# PCB_MCH_mordovia.net
KiCad netlist of a schematic drawn in Altium Designer
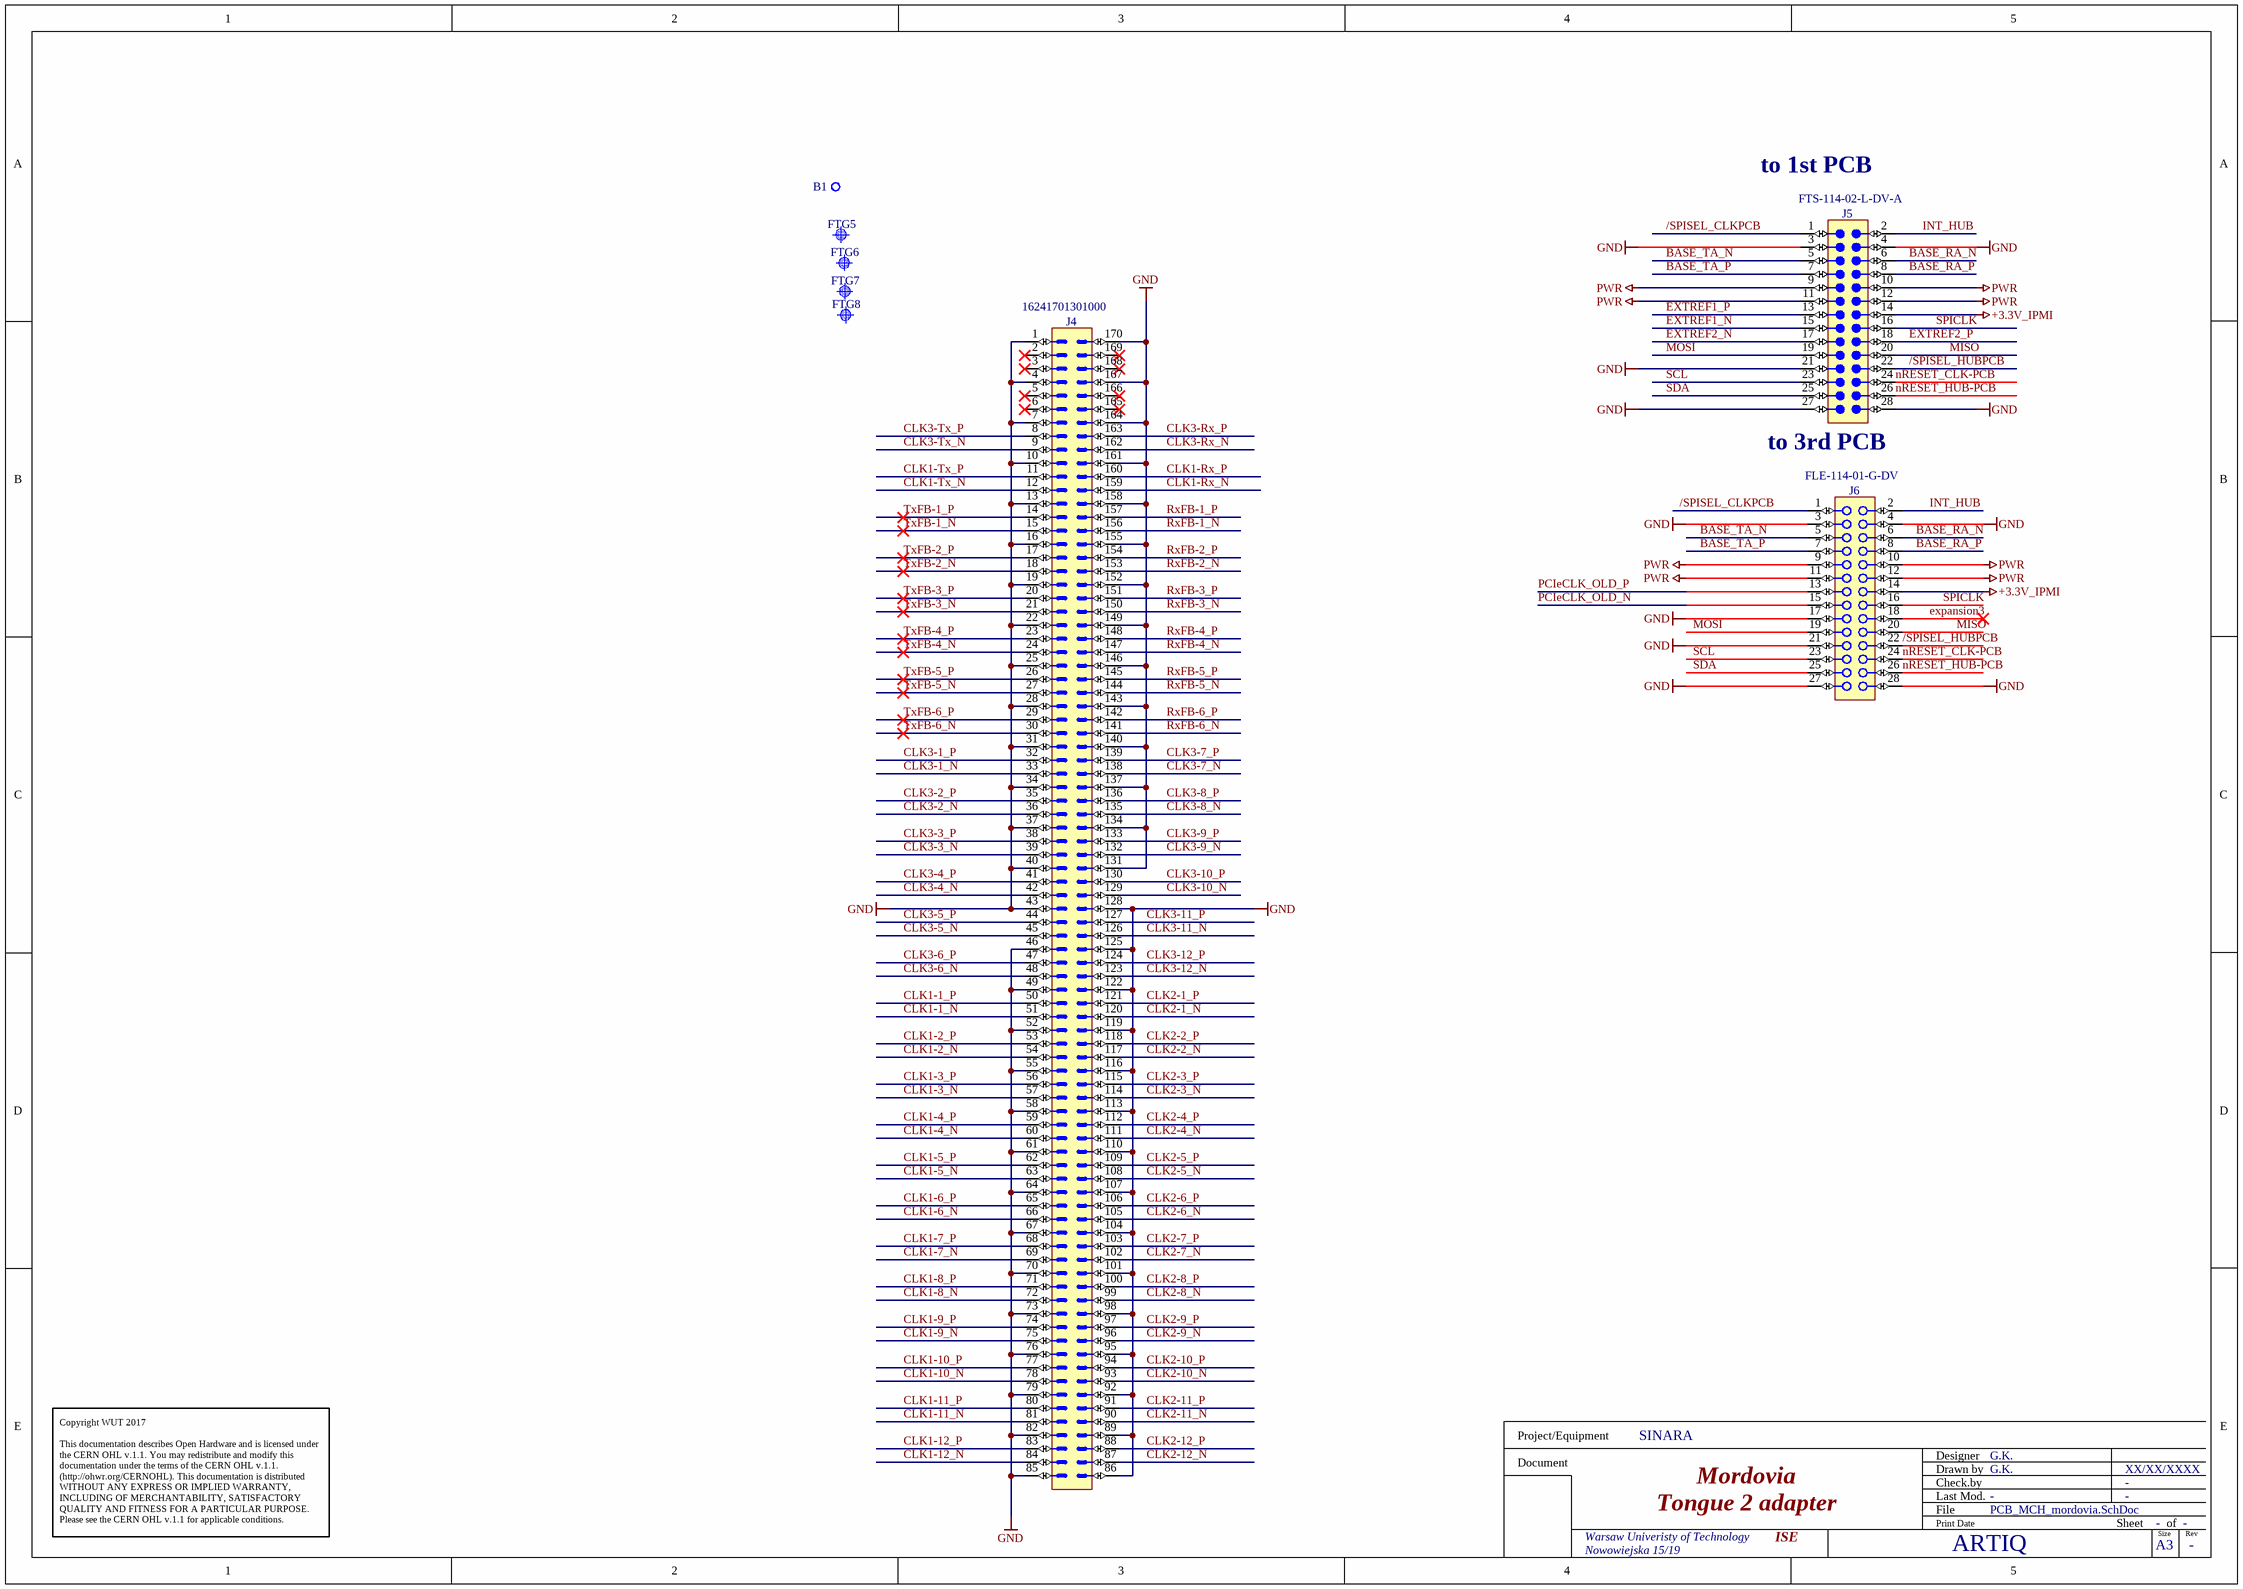
[diagram p0: PCB_MCH_mordovia.SchDoc]

(export (version "E")
  (design (tool "Eeschema 10.0.6"))
  (components
    (comp (ref "B1")
      (value "Non Plated Hole")
      (footprint "MTG520")
      (description "Single Terminal Socket")
      (fields (field (name "PART NUMBER") "NON-PLATED_HOLE5.2") (field (name "AUTHOR") "CERN DEM JMW"))
      (libsource (lib "Eletro-mechanical") (part "Single Terminal Socket"))
    )
    (comp (ref "FTG5")
      (value "Use only in PCB")
      (footprint "FIDUCIAL_TOP_C100-200")
      (description "Fiducial Target")
      (fields (field (name "PART NUMBER") "FIDUCIAL_TARGET_C100-200") (field (name "AUTHOR") "CERN DEM JLC"))
      (libsource (lib "Eletro-mechanical") (part "Fiducial Target"))
    )
    (comp (ref "FTG6")
      (value "Use only in PCB")
      (footprint "FIDUCIAL_TOP_S100-200")
      (description "Fiducial Target")
      (fields (field (name "PART NUMBER") "FIDUCIAL_TARGET_S100-200") (field (name "AUTHOR") "CERN DEM JLC"))
      (libsource (lib "Eletro-mechanical") (part "Fiducial Target"))
    )
    (comp (ref "FTG7")
      (value "Use only in PCB")
      (footprint "FIDUCIAL_TOP_S200-400")
      (description "Fiducial Target")
      (fields (field (name "PART NUMBER") "FIDUCIAL_TARGET_S200-400") (field (name "AUTHOR") "CERN DEM JLC"))
      (libsource (lib "Eletro-mechanical") (part "Fiducial Target"))
    )
    (comp (ref "FTG8")
      (value "Use only in PCB")
      (footprint "FIDUCIAL_TOP_S100-200")
      (description "Fiducial Target")
      (fields (field (name "PART NUMBER") "FIDUCIAL_TARGET_S100-200") (field (name "AUTHOR") "CERN DEM JLC"))
      (libsource (lib "Eletro-mechanical") (part "Fiducial Target"))
    )
    (comp (ref "J4")
      (value "~")
      (footprint "ITB_16241701301000")
      (description "Connector 170 Male")
      (fields
        (field (name "PART NUMBER") "ITB_16241701301000")
        (field (name "MANUFACTURER") "ITB ADVANCED CONNECTORS")
        (field (name "MANUFACTURER PART NUMBER") "16241701301000")
        (field (name "AUTHOR") "CERN DEM MR")
      )
      (libsource (lib "Connectors") (part "Connector 170 Male"))
    )
    (comp (ref "J5")
      (value "Header 28")
      (footprint "SAMTEC_FTS-114-02-L-DV-A")
      (description "Connector 28 Male")
      (fields
        (field (name "PART NUMBER") "SAMTEC_FTS-114-02-L-DV-A")
        (field (name "MANUFACTURER") "SAMTEC")
        (field (name "MANUFACTURER PART NUMBER") "FTS-114-02-L-DV-A")
        (field (name "AUTHOR") "CERN DEM MR")
      )
      (libsource (lib "Connectors") (part "Connector 28 Male"))
    )
    (comp (ref "J6")
      (value "Socket 28")
      (footprint "SAMTEC_FLE-114-01-G-DV")
      (description "Connector 28 Female")
      (fields
        (field (name "PART NUMBER") "SAMTEC_FLE-114-01-G-DV")
        (field (name "MANUFACTURER") "SAMTEC")
        (field (name "MANUFACTURER PART NUMBER") "FLE-114-01-G-DV")
        (field (name "AUTHOR") "CERN DEM MR")
      )
      (libsource (lib "Connectors") (part "Connector 28 Female"))
    )
  )
  (nets
    (net (code "1") (name "+3.3V_IPMI") (class "Default")
      (node (ref "J5") (pin "14") (pinfunction "14_14") (pintype "bidirectional"))
      (node (ref "J6") (pin "14") (pinfunction "14_14") (pintype "bidirectional"))
    )
    (net (code "2") (name "/BASE_RA_N") (class "Default")
      (node (ref "J5") (pin "6") (pinfunction "6_6") (pintype "bidirectional"))
      (node (ref "J6") (pin "6") (pinfunction "6_6") (pintype "bidirectional"))
    )
    (net (code "3") (name "/BASE_RA_P") (class "Default")
      (node (ref "J5") (pin "8") (pinfunction "8_8") (pintype "bidirectional"))
      (node (ref "J6") (pin "8") (pinfunction "8_8") (pintype "bidirectional"))
    )
    (net (code "4") (name "/BASE_TA_N") (class "Default")
      (node (ref "J5") (pin "5") (pinfunction "5_5") (pintype "bidirectional"))
      (node (ref "J6") (pin "5") (pinfunction "5_5") (pintype "bidirectional"))
    )
    (net (code "5") (name "/BASE_TA_P") (class "Default")
      (node (ref "J5") (pin "7") (pinfunction "7_7") (pintype "bidirectional"))
      (node (ref "J6") (pin "7") (pinfunction "7_7") (pintype "bidirectional"))
    )
    (net (code "6") (name "/CLK1-1_N") (class "Default")
      (node (ref "J4") (pin "51") (pinfunction "101_51") (pintype "bidirectional"))
    )
    (net (code "7") (name "/CLK1-1_P") (class "Default")
      (node (ref "J4") (pin "50") (pinfunction "99_50") (pintype "bidirectional"))
    )
    (net (code "8") (name "/CLK1-2_N") (class "Default")
      (node (ref "J4") (pin "54") (pinfunction "107_54") (pintype "bidirectional"))
    )
    (net (code "9") (name "/CLK1-2_P") (class "Default")
      (node (ref "J4") (pin "53") (pinfunction "105_53") (pintype "bidirectional"))
    )
    (net (code "10") (name "/CLK1-3_N") (class "Default")
      (node (ref "J4") (pin "57") (pinfunction "113_57") (pintype "bidirectional"))
    )
    (net (code "11") (name "/CLK1-3_P") (class "Default")
      (node (ref "J4") (pin "56") (pinfunction "111_56") (pintype "bidirectional"))
    )
    (net (code "12") (name "/CLK1-4_N") (class "Default")
      (node (ref "J4") (pin "60") (pinfunction "119_60") (pintype "bidirectional"))
    )
    (net (code "13") (name "/CLK1-4_P") (class "Default")
      (node (ref "J4") (pin "59") (pinfunction "117_59") (pintype "bidirectional"))
    )
    (net (code "14") (name "/CLK1-5_N") (class "Default")
      (node (ref "J4") (pin "63") (pinfunction "75_63") (pintype "bidirectional"))
    )
    (net (code "15") (name "/CLK1-5_P") (class "Default")
      (node (ref "J4") (pin "62") (pinfunction "73_62") (pintype "bidirectional"))
    )
    (net (code "16") (name "/CLK1-6_N") (class "Default")
      (node (ref "J4") (pin "66") (pinfunction "81_66") (pintype "bidirectional"))
    )
    (net (code "17") (name "/CLK1-6_P") (class "Default")
      (node (ref "J4") (pin "65") (pinfunction "79_65") (pintype "bidirectional"))
    )
    (net (code "18") (name "/CLK1-7_N") (class "Default")
      (node (ref "J4") (pin "69") (pinfunction "87_69") (pintype "bidirectional"))
    )
    (net (code "19") (name "/CLK1-7_P") (class "Default")
      (node (ref "J4") (pin "68") (pinfunction "85_68") (pintype "bidirectional"))
    )
    (net (code "20") (name "/CLK1-8_N") (class "Default")
      (node (ref "J4") (pin "72") (pinfunction "93_72") (pintype "bidirectional"))
    )
    (net (code "21") (name "/CLK1-8_P") (class "Default")
      (node (ref "J4") (pin "71") (pinfunction "91_71") (pintype "bidirectional"))
    )
    (net (code "22") (name "/CLK1-9_N") (class "Default")
      (node (ref "J4") (pin "75") (pinfunction "99_75") (pintype "bidirectional"))
    )
    (net (code "23") (name "/CLK1-9_P") (class "Default")
      (node (ref "J4") (pin "74") (pinfunction "97_74") (pintype "bidirectional"))
    )
    (net (code "24") (name "/CLK1-10_N") (class "Default")
      (node (ref "J4") (pin "78") (pinfunction "105_78") (pintype "bidirectional"))
    )
    (net (code "25") (name "/CLK1-10_P") (class "Default")
      (node (ref "J4") (pin "77") (pinfunction "103_77") (pintype "bidirectional"))
    )
    (net (code "26") (name "/CLK1-11_N") (class "Default")
      (node (ref "J4") (pin "81") (pinfunction "111_81") (pintype "bidirectional"))
    )
    (net (code "27") (name "/CLK1-11_P") (class "Default")
      (node (ref "J4") (pin "80") (pinfunction "109_80") (pintype "bidirectional"))
    )
    (net (code "28") (name "/CLK1-12_N") (class "Default")
      (node (ref "J4") (pin "84") (pinfunction "117_84") (pintype "bidirectional"))
    )
    (net (code "29") (name "/CLK1-12_P") (class "Default")
      (node (ref "J4") (pin "83") (pinfunction "115_83") (pintype "bidirectional"))
    )
    (net (code "30") (name "/CLK1-Rx_N") (class "Default")
      (node (ref "J4") (pin "159") (pinfunction "159_159") (pintype "bidirectional"))
    )
    (net (code "31") (name "/CLK1-Rx_P") (class "Default")
      (node (ref "J4") (pin "160") (pinfunction "160_160") (pintype "bidirectional"))
    )
    (net (code "32") (name "/CLK1-Tx_N") (class "Default")
      (node (ref "J4") (pin "12") (pinfunction "23_12") (pintype "bidirectional"))
    )
    (net (code "33") (name "/CLK1-Tx_P") (class "Default")
      (node (ref "J4") (pin "11") (pinfunction "21_11") (pintype "bidirectional"))
    )
    (net (code "34") (name "/CLK2-1_N") (class "Default")
      (node (ref "J4") (pin "120") (pinfunction "120_120") (pintype "bidirectional"))
    )
    (net (code "35") (name "/CLK2-1_P") (class "Default")
      (node (ref "J4") (pin "121") (pinfunction "121_121") (pintype "bidirectional"))
    )
    (net (code "36") (name "/CLK2-2_N") (class "Default")
      (node (ref "J4") (pin "117") (pinfunction "117_117") (pintype "bidirectional"))
    )
    (net (code "37") (name "/CLK2-2_P") (class "Default")
      (node (ref "J4") (pin "118") (pinfunction "118_118") (pintype "bidirectional"))
    )
    (net (code "38") (name "/CLK2-3_N") (class "Default")
      (node (ref "J4") (pin "114") (pinfunction "114_114") (pintype "bidirectional"))
    )
    (net (code "39") (name "/CLK2-3_P") (class "Default")
      (node (ref "J4") (pin "115") (pinfunction "115_115") (pintype "bidirectional"))
    )
    (net (code "40") (name "/CLK2-4_N") (class "Default")
      (node (ref "J4") (pin "111") (pinfunction "111_111") (pintype "bidirectional"))
    )
    (net (code "41") (name "/CLK2-4_P") (class "Default")
      (node (ref "J4") (pin "112") (pinfunction "112_112") (pintype "bidirectional"))
    )
    (net (code "42") (name "/CLK2-5_N") (class "Default")
      (node (ref "J4") (pin "108") (pinfunction "108_108") (pintype "bidirectional"))
    )
    (net (code "43") (name "/CLK2-5_P") (class "Default")
      (node (ref "J4") (pin "109") (pinfunction "109_109") (pintype "bidirectional"))
    )
    (net (code "44") (name "/CLK2-6_N") (class "Default")
      (node (ref "J4") (pin "105") (pinfunction "105_105") (pintype "bidirectional"))
    )
    (net (code "45") (name "/CLK2-6_P") (class "Default")
      (node (ref "J4") (pin "106") (pinfunction "106_106") (pintype "bidirectional"))
    )
    (net (code "46") (name "/CLK2-7_N") (class "Default")
      (node (ref "J4") (pin "102") (pinfunction "102_102") (pintype "bidirectional"))
    )
    (net (code "47") (name "/CLK2-7_P") (class "Default")
      (node (ref "J4") (pin "103") (pinfunction "103_103") (pintype "bidirectional"))
    )
    (net (code "48") (name "/CLK2-8_N") (class "Default")
      (node (ref "J4") (pin "99") (pinfunction "99_99") (pintype "bidirectional"))
    )
    (net (code "49") (name "/CLK2-8_P") (class "Default")
      (node (ref "J4") (pin "100") (pinfunction "100_100") (pintype "bidirectional"))
    )
    (net (code "50") (name "/CLK2-9_N") (class "Default")
      (node (ref "J4") (pin "96") (pinfunction "96_96") (pintype "bidirectional"))
    )
    (net (code "51") (name "/CLK2-9_P") (class "Default")
      (node (ref "J4") (pin "97") (pinfunction "97_97") (pintype "bidirectional"))
    )
    (net (code "52") (name "/CLK2-10_N") (class "Default")
      (node (ref "J4") (pin "93") (pinfunction "93_93") (pintype "bidirectional"))
    )
    (net (code "53") (name "/CLK2-10_P") (class "Default")
      (node (ref "J4") (pin "94") (pinfunction "94_94") (pintype "bidirectional"))
    )
    (net (code "54") (name "/CLK2-11_N") (class "Default")
      (node (ref "J4") (pin "90") (pinfunction "90_90") (pintype "bidirectional"))
    )
    (net (code "55") (name "/CLK2-11_P") (class "Default")
      (node (ref "J4") (pin "91") (pinfunction "91_91") (pintype "bidirectional"))
    )
    (net (code "56") (name "/CLK2-12_N") (class "Default")
      (node (ref "J4") (pin "87") (pinfunction "87_87") (pintype "bidirectional"))
    )
    (net (code "57") (name "/CLK2-12_P") (class "Default")
      (node (ref "J4") (pin "88") (pinfunction "88_88") (pintype "bidirectional"))
    )
    (net (code "58") (name "/CLK3-1_N") (class "Default")
      (node (ref "J4") (pin "33") (pinfunction "65_33") (pintype "bidirectional"))
    )
    (net (code "59") (name "/CLK3-1_P") (class "Default")
      (node (ref "J4") (pin "32") (pinfunction "63_32") (pintype "bidirectional"))
    )
    (net (code "60") (name "/CLK3-2_N") (class "Default")
      (node (ref "J4") (pin "36") (pinfunction "71_36") (pintype "bidirectional"))
    )
    (net (code "61") (name "/CLK3-2_P") (class "Default")
      (node (ref "J4") (pin "35") (pinfunction "69_35") (pintype "bidirectional"))
    )
    (net (code "62") (name "/CLK3-3_N") (class "Default")
      (node (ref "J4") (pin "39") (pinfunction "77_39") (pintype "bidirectional"))
    )
    (net (code "63") (name "/CLK3-3_P") (class "Default")
      (node (ref "J4") (pin "38") (pinfunction "75_38") (pintype "bidirectional"))
    )
    (net (code "64") (name "/CLK3-4_N") (class "Default")
      (node (ref "J4") (pin "42") (pinfunction "83_42") (pintype "bidirectional"))
    )
    (net (code "65") (name "/CLK3-4_P") (class "Default")
      (node (ref "J4") (pin "41") (pinfunction "81_41") (pintype "bidirectional"))
    )
    (net (code "66") (name "/CLK3-5_N") (class "Default")
      (node (ref "J4") (pin "45") (pinfunction "89_45") (pintype "bidirectional"))
    )
    (net (code "67") (name "/CLK3-5_P") (class "Default")
      (node (ref "J4") (pin "44") (pinfunction "87_44") (pintype "bidirectional"))
    )
    (net (code "68") (name "/CLK3-6_N") (class "Default")
      (node (ref "J4") (pin "48") (pinfunction "95_48") (pintype "bidirectional"))
    )
    (net (code "69") (name "/CLK3-6_P") (class "Default")
      (node (ref "J4") (pin "47") (pinfunction "93_47") (pintype "bidirectional"))
    )
    (net (code "70") (name "/CLK3-7_N") (class "Default")
      (node (ref "J4") (pin "138") (pinfunction "138_138") (pintype "bidirectional"))
    )
    (net (code "71") (name "/CLK3-7_P") (class "Default")
      (node (ref "J4") (pin "139") (pinfunction "139_139") (pintype "bidirectional"))
    )
    (net (code "72") (name "/CLK3-8_N") (class "Default")
      (node (ref "J4") (pin "135") (pinfunction "135_135") (pintype "bidirectional"))
    )
    (net (code "73") (name "/CLK3-8_P") (class "Default")
      (node (ref "J4") (pin "136") (pinfunction "136_136") (pintype "bidirectional"))
    )
    (net (code "74") (name "/CLK3-9_N") (class "Default")
      (node (ref "J4") (pin "132") (pinfunction "132_132") (pintype "bidirectional"))
    )
    (net (code "75") (name "/CLK3-9_P") (class "Default")
      (node (ref "J4") (pin "133") (pinfunction "133_133") (pintype "bidirectional"))
    )
    (net (code "76") (name "/CLK3-10_N") (class "Default")
      (node (ref "J4") (pin "129") (pinfunction "129_129") (pintype "bidirectional"))
    )
    (net (code "77") (name "/CLK3-10_P") (class "Default")
      (node (ref "J4") (pin "130") (pinfunction "130_130") (pintype "bidirectional"))
    )
    (net (code "78") (name "/CLK3-11_N") (class "Default")
      (node (ref "J4") (pin "126") (pinfunction "126_126") (pintype "bidirectional"))
    )
    (net (code "79") (name "/CLK3-11_P") (class "Default")
      (node (ref "J4") (pin "127") (pinfunction "127_127") (pintype "bidirectional"))
    )
    (net (code "80") (name "/CLK3-12_N") (class "Default")
      (node (ref "J4") (pin "123") (pinfunction "123_123") (pintype "bidirectional"))
    )
    (net (code "81") (name "/CLK3-12_P") (class "Default")
      (node (ref "J4") (pin "124") (pinfunction "124_124") (pintype "bidirectional"))
    )
    (net (code "82") (name "/CLK3-Rx_N") (class "Default")
      (node (ref "J4") (pin "162") (pinfunction "162_162") (pintype "bidirectional"))
    )
    (net (code "83") (name "/CLK3-Rx_P") (class "Default")
      (node (ref "J4") (pin "163") (pinfunction "163_163") (pintype "bidirectional"))
    )
    (net (code "84") (name "/CLK3-Tx_N") (class "Default")
      (node (ref "J4") (pin "9") (pinfunction "17_9") (pintype "bidirectional"))
    )
    (net (code "85") (name "/CLK3-Tx_P") (class "Default")
      (node (ref "J4") (pin "8") (pinfunction "15_8") (pintype "bidirectional"))
    )
    (net (code "86") (name "/EXTREF1_N") (class "Default")
      (node (ref "J5") (pin "15") (pinfunction "15_15") (pintype "bidirectional"))
    )
    (net (code "87") (name "/EXTREF1_P") (class "Default")
      (node (ref "J5") (pin "13") (pinfunction "13_13") (pintype "bidirectional"))
    )
    (net (code "88") (name "/EXTREF2_N") (class "Default")
      (node (ref "J5") (pin "17") (pinfunction "17_17") (pintype "bidirectional"))
    )
    (net (code "89") (name "/EXTREF2_P") (class "Default")
      (node (ref "J5") (pin "18") (pinfunction "18_18") (pintype "bidirectional"))
    )
    (net (code "90") (name "/INT_HUB") (class "Default")
      (node (ref "J5") (pin "2") (pinfunction "2_2") (pintype "bidirectional"))
      (node (ref "J6") (pin "2") (pinfunction "2_2") (pintype "bidirectional"))
    )
    (net (code "91") (name "/MISO") (class "Default")
      (node (ref "J5") (pin "20") (pinfunction "20_20") (pintype "bidirectional"))
      (node (ref "J6") (pin "20") (pinfunction "20_20") (pintype "bidirectional"))
    )
    (net (code "92") (name "/MOSI") (class "Default")
      (node (ref "J5") (pin "19") (pinfunction "19_19") (pintype "bidirectional"))
      (node (ref "J6") (pin "19") (pinfunction "19_19") (pintype "bidirectional"))
    )
    (net (code "93") (name "/PCIeCLK_OLD_N") (class "Default")
      (node (ref "J6") (pin "15") (pinfunction "15_15") (pintype "bidirectional"))
    )
    (net (code "94") (name "/PCIeCLK_OLD_P") (class "Default")
      (node (ref "J6") (pin "13") (pinfunction "13_13") (pintype "bidirectional"))
    )
    (net (code "95") (name "/RxFB-1_N") (class "Default")
      (node (ref "J4") (pin "156") (pinfunction "156_156") (pintype "bidirectional"))
    )
    (net (code "96") (name "/RxFB-1_P") (class "Default")
      (node (ref "J4") (pin "157") (pinfunction "157_157") (pintype "bidirectional"))
    )
    (net (code "97") (name "/RxFB-2_N") (class "Default")
      (node (ref "J4") (pin "153") (pinfunction "153_153") (pintype "bidirectional"))
    )
    (net (code "98") (name "/RxFB-2_P") (class "Default")
      (node (ref "J4") (pin "154") (pinfunction "154_154") (pintype "bidirectional"))
    )
    (net (code "99") (name "/RxFB-3_N") (class "Default")
      (node (ref "J4") (pin "150") (pinfunction "150_150") (pintype "bidirectional"))
    )
    (net (code "100") (name "/RxFB-3_P") (class "Default")
      (node (ref "J4") (pin "151") (pinfunction "151_151") (pintype "bidirectional"))
    )
    (net (code "101") (name "/RxFB-4_N") (class "Default")
      (node (ref "J4") (pin "147") (pinfunction "147_147") (pintype "bidirectional"))
    )
    (net (code "102") (name "/RxFB-4_P") (class "Default")
      (node (ref "J4") (pin "148") (pinfunction "148_148") (pintype "bidirectional"))
    )
    (net (code "103") (name "/RxFB-5_N") (class "Default")
      (node (ref "J4") (pin "144") (pinfunction "144_144") (pintype "bidirectional"))
    )
    (net (code "104") (name "/RxFB-5_P") (class "Default")
      (node (ref "J4") (pin "145") (pinfunction "145_145") (pintype "bidirectional"))
    )
    (net (code "105") (name "/RxFB-6_N") (class "Default")
      (node (ref "J4") (pin "141") (pinfunction "141_141") (pintype "bidirectional"))
    )
    (net (code "106") (name "/RxFB-6_P") (class "Default")
      (node (ref "J4") (pin "142") (pinfunction "142_142") (pintype "bidirectional"))
    )
    (net (code "107") (name "/SCL") (class "Default")
      (node (ref "J5") (pin "23") (pinfunction "23_23") (pintype "bidirectional"))
      (node (ref "J6") (pin "23") (pinfunction "23_23") (pintype "bidirectional"))
    )
    (net (code "108") (name "/SDA") (class "Default")
      (node (ref "J5") (pin "25") (pinfunction "25_25") (pintype "bidirectional"))
      (node (ref "J6") (pin "25") (pinfunction "25_25") (pintype "bidirectional"))
    )
    (net (code "109") (name "/SPICLK") (class "Default")
      (node (ref "J5") (pin "16") (pinfunction "16_16") (pintype "bidirectional"))
      (node (ref "J6") (pin "16") (pinfunction "16_16") (pintype "bidirectional"))
    )
    (net (code "122") (name "/TxFB-1_N") (class "Default")
      (node (ref "J4") (pin "15") (pinfunction "29_15") (pintype "bidirectional"))
    )
    (net (code "123") (name "/TxFB-1_P") (class "Default")
      (node (ref "J4") (pin "14") (pinfunction "27_14") (pintype "bidirectional"))
    )
    (net (code "124") (name "/TxFB-2_N") (class "Default")
      (node (ref "J4") (pin "18") (pinfunction "35_18") (pintype "bidirectional"))
    )
    (net (code "125") (name "/TxFB-2_P") (class "Default")
      (node (ref "J4") (pin "17") (pinfunction "33_17") (pintype "bidirectional"))
    )
    (net (code "126") (name "/TxFB-3_N") (class "Default")
      (node (ref "J4") (pin "21") (pinfunction "41_21") (pintype "bidirectional"))
    )
    (net (code "127") (name "/TxFB-3_P") (class "Default")
      (node (ref "J4") (pin "20") (pinfunction "39_20") (pintype "bidirectional"))
    )
    (net (code "128") (name "/TxFB-4_N") (class "Default")
      (node (ref "J4") (pin "24") (pinfunction "47_24") (pintype "bidirectional"))
    )
    (net (code "129") (name "/TxFB-4_P") (class "Default")
      (node (ref "J4") (pin "23") (pinfunction "45_23") (pintype "bidirectional"))
    )
    (net (code "130") (name "/TxFB-5_N") (class "Default")
      (node (ref "J4") (pin "27") (pinfunction "53_27") (pintype "bidirectional"))
    )
    (net (code "131") (name "/TxFB-5_P") (class "Default")
      (node (ref "J4") (pin "26") (pinfunction "51_26") (pintype "bidirectional"))
    )
    (net (code "132") (name "/TxFB-6_N") (class "Default")
      (node (ref "J4") (pin "30") (pinfunction "59_30") (pintype "bidirectional"))
    )
    (net (code "133") (name "/TxFB-6_P") (class "Default")
      (node (ref "J4") (pin "29") (pinfunction "57_29") (pintype "bidirectional"))
    )
    (net (code "134") (name "/expansion3") (class "Default")
      (node (ref "J6") (pin "18") (pinfunction "18_18") (pintype "bidirectional+no_connect"))
    )
    (net (code "135") (name "/nRESET_CLK-PCB") (class "Default")
      (node (ref "J5") (pin "24") (pinfunction "24_24") (pintype "bidirectional"))
      (node (ref "J6") (pin "24") (pinfunction "24_24") (pintype "bidirectional"))
    )
    (net (code "136") (name "/nRESET_HUB-PCB") (class "Default")
      (node (ref "J5") (pin "26") (pinfunction "26_26") (pintype "bidirectional"))
      (node (ref "J6") (pin "26") (pinfunction "26_26") (pintype "bidirectional"))
    )
    (net (code "137") (name "/{slash}SPISEL_CLKPCB") (class "Default")
      (node (ref "J5") (pin "1") (pinfunction "1_1") (pintype "bidirectional"))
      (node (ref "J6") (pin "1") (pinfunction "1_1") (pintype "bidirectional"))
    )
    (net (code "138") (name "/{slash}SPISEL_HUBPCB") (class "Default")
      (node (ref "J5") (pin "22") (pinfunction "22_22") (pintype "bidirectional"))
      (node (ref "J6") (pin "22") (pinfunction "22_22") (pintype "bidirectional"))
    )
    (net (code "139") (name "GND") (class "Default")
      (node (ref "J4") (pin "1") (pinfunction "1_1") (pintype "bidirectional"))
      (node (ref "J4") (pin "10") (pinfunction "19_10") (pintype "bidirectional"))
      (node (ref "J4") (pin "101") (pinfunction "101_101") (pintype "bidirectional"))
      (node (ref "J4") (pin "104") (pinfunction "104_104") (pintype "bidirectional"))
      (node (ref "J4") (pin "107") (pinfunction "107_107") (pintype "bidirectional"))
      (node (ref "J4") (pin "110") (pinfunction "110_110") (pintype "bidirectional"))
      (node (ref "J4") (pin "113") (pinfunction "113_113") (pintype "bidirectional"))
      (node (ref "J4") (pin "116") (pinfunction "116_116") (pintype "bidirectional"))
      (node (ref "J4") (pin "119") (pinfunction "119_119") (pintype "bidirectional"))
      (node (ref "J4") (pin "122") (pinfunction "122_122") (pintype "bidirectional"))
      (node (ref "J4") (pin "125") (pinfunction "125_125") (pintype "bidirectional"))
      (node (ref "J4") (pin "128") (pinfunction "128_128") (pintype "bidirectional"))
      (node (ref "J4") (pin "13") (pinfunction "25_13") (pintype "bidirectional"))
      (node (ref "J4") (pin "131") (pinfunction "131_131") (pintype "bidirectional"))
      (node (ref "J4") (pin "134") (pinfunction "134_134") (pintype "bidirectional"))
      (node (ref "J4") (pin "137") (pinfunction "137_137") (pintype "bidirectional"))
      (node (ref "J4") (pin "140") (pinfunction "140_140") (pintype "bidirectional"))
      (node (ref "J4") (pin "143") (pinfunction "143_143") (pintype "bidirectional"))
      (node (ref "J4") (pin "146") (pinfunction "146_146") (pintype "bidirectional"))
      (node (ref "J4") (pin "149") (pinfunction "149_149") (pintype "bidirectional"))
      (node (ref "J4") (pin "152") (pinfunction "152_152") (pintype "bidirectional"))
      (node (ref "J4") (pin "155") (pinfunction "155_155") (pintype "bidirectional"))
      (node (ref "J4") (pin "158") (pinfunction "158_158") (pintype "bidirectional"))
      (node (ref "J4") (pin "16") (pinfunction "31_16") (pintype "bidirectional"))
      (node (ref "J4") (pin "161") (pinfunction "161_161") (pintype "bidirectional"))
      (node (ref "J4") (pin "164") (pinfunction "164_164") (pintype "bidirectional"))
      (node (ref "J4") (pin "167") (pinfunction "167_167") (pintype "bidirectional"))
      (node (ref "J4") (pin "170") (pinfunction "170_170") (pintype "bidirectional"))
      (node (ref "J4") (pin "19") (pinfunction "37_19") (pintype "bidirectional"))
      (node (ref "J4") (pin "22") (pinfunction "43_22") (pintype "bidirectional"))
      (node (ref "J4") (pin "25") (pinfunction "49_25") (pintype "bidirectional"))
      (node (ref "J4") (pin "28") (pinfunction "55_28") (pintype "bidirectional"))
      (node (ref "J4") (pin "31") (pinfunction "61_31") (pintype "bidirectional"))
      (node (ref "J4") (pin "34") (pinfunction "67_34") (pintype "bidirectional"))
      (node (ref "J4") (pin "37") (pinfunction "73_37") (pintype "bidirectional"))
      (node (ref "J4") (pin "4") (pinfunction "7_4") (pintype "bidirectional"))
      (node (ref "J4") (pin "40") (pinfunction "79_40") (pintype "bidirectional"))
      (node (ref "J4") (pin "43") (pinfunction "85_43") (pintype "bidirectional"))
      (node (ref "J4") (pin "46") (pinfunction "91_46") (pintype "bidirectional"))
      (node (ref "J4") (pin "49") (pinfunction "97_49") (pintype "bidirectional"))
      (node (ref "J4") (pin "52") (pinfunction "103_52") (pintype "bidirectional"))
      (node (ref "J4") (pin "55") (pinfunction "109_55") (pintype "bidirectional"))
      (node (ref "J4") (pin "58") (pinfunction "115_58") (pintype "bidirectional"))
      (node (ref "J4") (pin "61") (pinfunction "71_61") (pintype "bidirectional"))
      (node (ref "J4") (pin "64") (pinfunction "77_64") (pintype "bidirectional"))
      (node (ref "J4") (pin "67") (pinfunction "83_67") (pintype "bidirectional"))
      (node (ref "J4") (pin "7") (pinfunction "13_7") (pintype "bidirectional"))
      (node (ref "J4") (pin "70") (pinfunction "89_70") (pintype "bidirectional"))
      (node (ref "J4") (pin "73") (pinfunction "95_73") (pintype "bidirectional"))
      (node (ref "J4") (pin "76") (pinfunction "101_76") (pintype "bidirectional"))
      (node (ref "J4") (pin "79") (pinfunction "107_79") (pintype "bidirectional"))
      (node (ref "J4") (pin "82") (pinfunction "113_82") (pintype "bidirectional"))
      (node (ref "J4") (pin "85") (pinfunction "119_85") (pintype "bidirectional"))
      (node (ref "J4") (pin "86") (pinfunction "86_86") (pintype "bidirectional"))
      (node (ref "J4") (pin "89") (pinfunction "89_89") (pintype "bidirectional"))
      (node (ref "J4") (pin "92") (pinfunction "92_92") (pintype "bidirectional"))
      (node (ref "J4") (pin "95") (pinfunction "95_95") (pintype "bidirectional"))
      (node (ref "J4") (pin "98") (pinfunction "98_98") (pintype "bidirectional"))
      (node (ref "J5") (pin "21") (pinfunction "21_21") (pintype "bidirectional"))
      (node (ref "J5") (pin "27") (pinfunction "27_27") (pintype "bidirectional"))
      (node (ref "J5") (pin "28") (pinfunction "28_28") (pintype "bidirectional"))
      (node (ref "J5") (pin "3") (pinfunction "3_3") (pintype "bidirectional"))
      (node (ref "J5") (pin "4") (pinfunction "4_4") (pintype "bidirectional"))
      (node (ref "J6") (pin "17") (pinfunction "17_17") (pintype "bidirectional"))
      (node (ref "J6") (pin "21") (pinfunction "21_21") (pintype "bidirectional"))
      (node (ref "J6") (pin "27") (pinfunction "27_27") (pintype "bidirectional"))
      (node (ref "J6") (pin "28") (pinfunction "28_28") (pintype "bidirectional"))
      (node (ref "J6") (pin "3") (pinfunction "3_3") (pintype "bidirectional"))
      (node (ref "J6") (pin "4") (pinfunction "4_4") (pintype "bidirectional"))
    )
    (net (code "140") (name "PWR") (class "Default")
      (node (ref "J5") (pin "10") (pinfunction "10_10") (pintype "bidirectional"))
      (node (ref "J5") (pin "11") (pinfunction "11_11") (pintype "bidirectional"))
      (node (ref "J5") (pin "12") (pinfunction "12_12") (pintype "bidirectional"))
      (node (ref "J5") (pin "9") (pinfunction "9_9") (pintype "bidirectional"))
      (node (ref "J6") (pin "10") (pinfunction "10_10") (pintype "bidirectional"))
      (node (ref "J6") (pin "11") (pinfunction "11_11") (pintype "bidirectional"))
      (node (ref "J6") (pin "12") (pinfunction "12_12") (pintype "bidirectional"))
      (node (ref "J6") (pin "9") (pinfunction "9_9") (pintype "bidirectional"))
    )
    (net (code "141") (name "unconnected-(B1-Pad1)") (class "Default")
      (node (ref "B1") (pin "1") (pinfunction "1_1") (pintype "bidirectional"))
    )
    (net (code "142") (name "unconnected-(J4-3-Pad2)") (class "Default")
      (node (ref "J4") (pin "2") (pinfunction "3_2") (pintype "bidirectional+no_connect"))
    )
    (net (code "143") (name "unconnected-(J4-5-Pad3)") (class "Default")
      (node (ref "J4") (pin "3") (pinfunction "5_3") (pintype "bidirectional+no_connect"))
    )
    (net (code "144") (name "unconnected-(J4-9-Pad5)") (class "Default")
      (node (ref "J4") (pin "5") (pinfunction "9_5") (pintype "bidirectional+no_connect"))
    )
    (net (code "145") (name "unconnected-(J4-11-Pad6)") (class "Default")
      (node (ref "J4") (pin "6") (pinfunction "11_6") (pintype "bidirectional+no_connect"))
    )
    (net (code "146") (name "unconnected-(J4-Pad165)") (class "Default")
      (node (ref "J4") (pin "165") (pinfunction "165_165") (pintype "bidirectional+no_connect"))
    )
    (net (code "147") (name "unconnected-(J4-Pad166)") (class "Default")
      (node (ref "J4") (pin "166") (pinfunction "166_166") (pintype "bidirectional+no_connect"))
    )
    (net (code "148") (name "unconnected-(J4-Pad168)") (class "Default")
      (node (ref "J4") (pin "168") (pinfunction "168_168") (pintype "bidirectional+no_connect"))
    )
    (net (code "149") (name "unconnected-(J4-Pad169)") (class "Default")
      (node (ref "J4") (pin "169") (pinfunction "169_169") (pintype "bidirectional+no_connect"))
    )
  )
)
